# ADL5611.net
KiCad netlist of a schematic drawn in Altium Designer
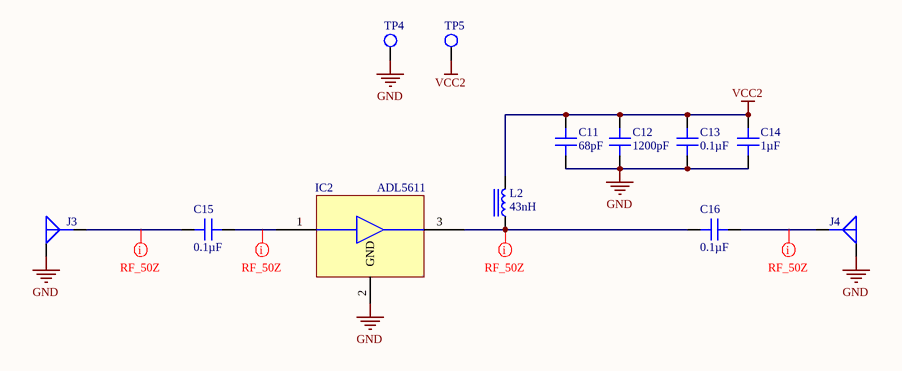
[diagram p0: ADL5611.SchDoc]

(export (version "E")
  (design (tool "Eeschema 10.0.6"))
  (components
    (comp (ref "C11")
      (value "68pF")
      (footprint "CAP 0402_1005")
      (description "CAP CER 68PF 50V C0G/NP0 0402")
      (fields
        (field (name "PART NUMBER") "GCM1555C1H680JA16D")
        (field (name "MANUFACTURER") "Murata Electronics")
      )
      (libsource (lib "Celestial Altium Library - altium_library") (part "Capacitor"))
    )
    (comp (ref "C12")
      (value "1200pF")
      (footprint "CAP 0402_1005")
      (description "CAP CER 1200PF 50V X7R 0402")
      (fields
        (field (name "PART NUMBER") "GCM155R71H122JA37D")
        (field (name "MANUFACTURER") "Murata Electronics")
      )
      (libsource (lib "Celestial Altium Library - altium_library") (part "Capacitor"))
    )
    (comp (ref "C13")
      (value "0.1µF")
      (footprint "CAP 0402_1005")
      (description "CAP CER 0.1UF 16V X7R 0402")
      (fields (field (name "PART NUMBER") "EMK105B7104KV-F") (field (name "MANUFACTURER") "Taiyo Yuden"))
      (libsource (lib "Celestial Altium Library - altium_library") (part "Capacitor"))
    )
    (comp (ref "C14")
      (value "1µF")
      (footprint "CAP 0402_1005")
      (description "CAP CER 1UF 10V X5R 0402")
      (fields
        (field (name "PART NUMBER") "CL05A105KP5NNNC")
        (field (name "MANUFACTURER") "Samsung Electro-Mechanics")
      )
      (libsource (lib "Celestial Altium Library - altium_library") (part "Capacitor"))
    )
    (comp (ref "C15")
      (value "0.1µF")
      (footprint "CAP 0402_1005")
      (description "CAP CER 0.1UF 16V X7R 0402")
      (fields (field (name "PART NUMBER") "EMK105B7104KV-F") (field (name "MANUFACTURER") "Taiyo Yuden"))
      (libsource (lib "Celestial Altium Library - altium_library") (part "Capacitor"))
    )
    (comp (ref "C16")
      (value "0.1µF")
      (footprint "CAP 0402_1005")
      (description "CAP CER 0.1UF 16V X7R 0402")
      (fields (field (name "PART NUMBER") "EMK105B7104KV-F") (field (name "MANUFACTURER") "Taiyo Yuden"))
      (libsource (lib "Celestial Altium Library - altium_library") (part "Capacitor"))
    )
    (comp (ref "IC2")
      (value "ADL5611")
      (footprint "Analog SOT-89")
      (description "IC AMP W-CDMA 30MHZ-6GHZ SOT89-3")
      (libsource (lib "IC") (part "ADL5611"))
    )
    (comp (ref "J3")
      (value "CON-SMA-EDGE-S")
      (footprint "CON-SMA-EDGE-S")
      (description "CONN SMA JACK STR EDGE MNT")
      (libsource (lib "Connector") (part "CON-SMA-EDGE-S"))
    )
    (comp (ref "J4")
      (value "CON-SMA-EDGE-S")
      (footprint "CON-SMA-EDGE-S")
      (description "CONN SMA JACK STR EDGE MNT")
      (libsource (lib "Connector") (part "CON-SMA-EDGE-S"))
    )
    (comp (ref "L2")
      (value "43nH")
      (footprint "0603HP")
      (description "Fixed Inductors 0603 43nH Unshld 2% 810mA 170mOhms")
      (libsource (lib "Inductor") (part "0603HP-43NXGLW"))
    )
    (comp (ref "TP4")
      (value "Test Point-THM")
      (footprint "KEYSTONE-THM-TestPoint")
      (description "THRU HOLE MOUNT TEST POINTS")
      (libsource (lib "Misc") (part "Test Point-THM"))
    )
    (comp (ref "TP5")
      (value "Test Point-THM")
      (footprint "KEYSTONE-THM-TestPoint")
      (description "THRU HOLE MOUNT TEST POINTS")
      (libsource (lib "Misc") (part "Test Point-THM"))
    )
  )
  (nets
    (net (code "1") (name "GND") (class "Default")
      (node (ref "C11") (pin "1") (pinfunction "1_1") (pintype "passive"))
      (node (ref "C12") (pin "1") (pinfunction "1_1") (pintype "passive"))
      (node (ref "C13") (pin "1") (pinfunction "1_1") (pintype "passive"))
      (node (ref "C14") (pin "1") (pinfunction "1_1") (pintype "passive"))
      (node (ref "IC2") (pin "2") (pinfunction "GND_2") (pintype "passive"))
      (node (ref "J3") (pin "2") (pinfunction "G_2") (pintype "passive"))
      (node (ref "J4") (pin "2") (pinfunction "G_2") (pintype "passive"))
      (node (ref "TP4") (pin "1") (pinfunction "TP_1") (pintype "passive"))
    )
    (net (code "2") (name "Net-(IC2-IN)") (class "Default")
      (node (ref "C15") (pin "1") (pinfunction "1_1") (pintype "passive"))
      (node (ref "IC2") (pin "1") (pinfunction "IN_1") (pintype "passive"))
    )
    (net (code "3") (name "Net-(IC2-OUT)") (class "Default")
      (node (ref "C16") (pin "2") (pinfunction "2_2") (pintype "passive"))
      (node (ref "IC2") (pin "3") (pinfunction "OUT_3") (pintype "passive"))
      (node (ref "L2") (pin "1") (pinfunction "1_1") (pintype "passive"))
    )
    (net (code "4") (name "Net-(J3-S)") (class "Default")
      (node (ref "C15") (pin "2") (pinfunction "2_2") (pintype "passive"))
      (node (ref "J3") (pin "1") (pinfunction "S_1") (pintype "passive"))
    )
    (net (code "5") (name "Net-(J4-S)") (class "Default")
      (node (ref "C16") (pin "1") (pinfunction "1_1") (pintype "passive"))
      (node (ref "J4") (pin "1") (pinfunction "S_1") (pintype "passive"))
    )
    (net (code "6") (name "VCC2") (class "Default")
      (node (ref "C11") (pin "2") (pinfunction "2_2") (pintype "passive"))
      (node (ref "C12") (pin "2") (pinfunction "2_2") (pintype "passive"))
      (node (ref "C13") (pin "2") (pinfunction "2_2") (pintype "passive"))
      (node (ref "C14") (pin "2") (pinfunction "2_2") (pintype "passive"))
      (node (ref "L2") (pin "2") (pinfunction "2_2") (pintype "passive"))
      (node (ref "TP5") (pin "1") (pinfunction "TP_1") (pintype "passive"))
    )
  )
)
